# version2.net
KiCad netlist of a schematic drawn in EAGLE
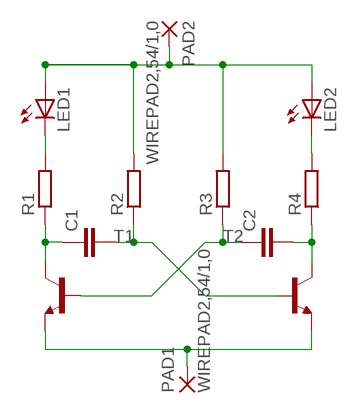
[diagram p0: schematic, sheet 1]

(export (version "E")
  (design (tool "Eeschema 10.0.6"))
  (components
    (comp (ref "C1")
      (value "C-EUC0603")
      (footprint "eagle-import:C0603")
      (libsource (lib "eagle-import") (part "C-EUC0603"))
    )
    (comp (ref "C2")
      (value "C-EUC0603")
      (footprint "eagle-import:C0603")
      (libsource (lib "eagle-import") (part "C-EUC0603"))
    )
    (comp (ref "LED1")
      (value "LEDSML0603")
      (footprint "eagle-import:SML0603")
      (libsource (lib "eagle-import") (part "LEDSML0603"))
    )
    (comp (ref "LED2")
      (value "LEDSML0603")
      (footprint "eagle-import:SML0603")
      (libsource (lib "eagle-import") (part "LEDSML0603"))
    )
    (comp (ref "PAD1")
      (value "WIREPAD2,54/1,0")
      (footprint "eagle-import:2,54_1,0")
      (libsource (lib "eagle-import") (part "WIREPAD2,54/1,0"))
    )
    (comp (ref "PAD2")
      (value "WIREPAD2,54/1,0")
      (footprint "eagle-import:2,54_1,0")
      (libsource (lib "eagle-import") (part "WIREPAD2,54/1,0"))
    )
    (comp (ref "R1")
      (value "R-EU_R0603")
      (footprint "eagle-import:R0603")
      (libsource (lib "eagle-import") (part "R-EU_R0603"))
    )
    (comp (ref "R2")
      (value "R-EU_R0603")
      (footprint "eagle-import:R0603")
      (libsource (lib "eagle-import") (part "R-EU_R0603"))
    )
    (comp (ref "R3")
      (value "R-EU_R0603")
      (footprint "eagle-import:R0603")
      (libsource (lib "eagle-import") (part "R-EU_R0603"))
    )
    (comp (ref "R4")
      (value "R-EU_R0603")
      (footprint "eagle-import:R0603")
      (libsource (lib "eagle-import") (part "R-EU_R0603"))
    )
    (comp (ref "T1")
      (value "MMBT2222ALT1-NPN-SOT23-BEC")
      (footprint "eagle-import:SOT23-BEC")
      (libsource (lib "eagle-import") (part "-NPN-SOT23-BECMMBT2222ALT1"))
    )
    (comp (ref "T2")
      (value "MMBT2222ALT1-NPN-SOT23-BEC")
      (footprint "eagle-import:SOT23-BEC")
      (libsource (lib "eagle-import") (part "-NPN-SOT23-BECMMBT2222ALT1"))
    )
  )
  (nets
    (net (code "1") (name "Net-(C1-Pad1)") (class "Default")
      (node (ref "C1") (pin "1") (pinfunction "1_1") (pintype "passive"))
      (node (ref "R1") (pin "1") (pinfunction "1_1") (pintype "passive"))
      (node (ref "T1") (pin "C") (pinfunction "C_C") (pintype "passive"))
    )
    (net (code "2") (name "Net-(C1-Pad2)") (class "Default")
      (node (ref "C1") (pin "2") (pinfunction "2_2") (pintype "passive"))
      (node (ref "R2") (pin "1") (pinfunction "1_1") (pintype "passive"))
      (node (ref "T2") (pin "B") (pinfunction "B_B") (pintype "passive"))
    )
    (net (code "3") (name "Net-(C2-Pad1)") (class "Default")
      (node (ref "C2") (pin "1") (pinfunction "1_1") (pintype "passive"))
      (node (ref "R3") (pin "1") (pinfunction "1_1") (pintype "passive"))
      (node (ref "T1") (pin "B") (pinfunction "B_B") (pintype "passive"))
    )
    (net (code "4") (name "Net-(C2-Pad2)") (class "Default")
      (node (ref "C2") (pin "2") (pinfunction "2_2") (pintype "passive"))
      (node (ref "R4") (pin "1") (pinfunction "1_1") (pintype "passive"))
      (node (ref "T2") (pin "C") (pinfunction "C_C") (pintype "passive"))
    )
    (net (code "5") (name "Net-(LED1-PadC)") (class "Default")
      (node (ref "LED1") (pin "C") (pinfunction "C_C") (pintype "passive"))
      (node (ref "R1") (pin "2") (pinfunction "2_2") (pintype "passive"))
    )
    (net (code "6") (name "Net-(LED2-PadC)") (class "Default")
      (node (ref "LED2") (pin "C") (pinfunction "C_C") (pintype "passive"))
      (node (ref "R4") (pin "2") (pinfunction "2_2") (pintype "passive"))
    )
    (net (code "7") (name "Net-(PAD1-P)") (class "Default")
      (node (ref "PAD1") (pin "1") (pinfunction "P_1") (pintype "passive"))
      (node (ref "T1") (pin "E") (pinfunction "E_E") (pintype "passive"))
      (node (ref "T2") (pin "E") (pinfunction "E_E") (pintype "passive"))
    )
    (net (code "8") (name "Net-(PAD2-P)") (class "Default")
      (node (ref "LED1") (pin "A") (pinfunction "A_A") (pintype "passive"))
      (node (ref "LED2") (pin "A") (pinfunction "A_A") (pintype "passive"))
      (node (ref "PAD2") (pin "1") (pinfunction "P_1") (pintype "passive"))
      (node (ref "R2") (pin "2") (pinfunction "2_2") (pintype "passive"))
      (node (ref "R3") (pin "2") (pinfunction "2_2") (pintype "passive"))
    )
  )
)
